# Integrated_Board_v1.net
KiCad netlist of a schematic drawn in EAGLE
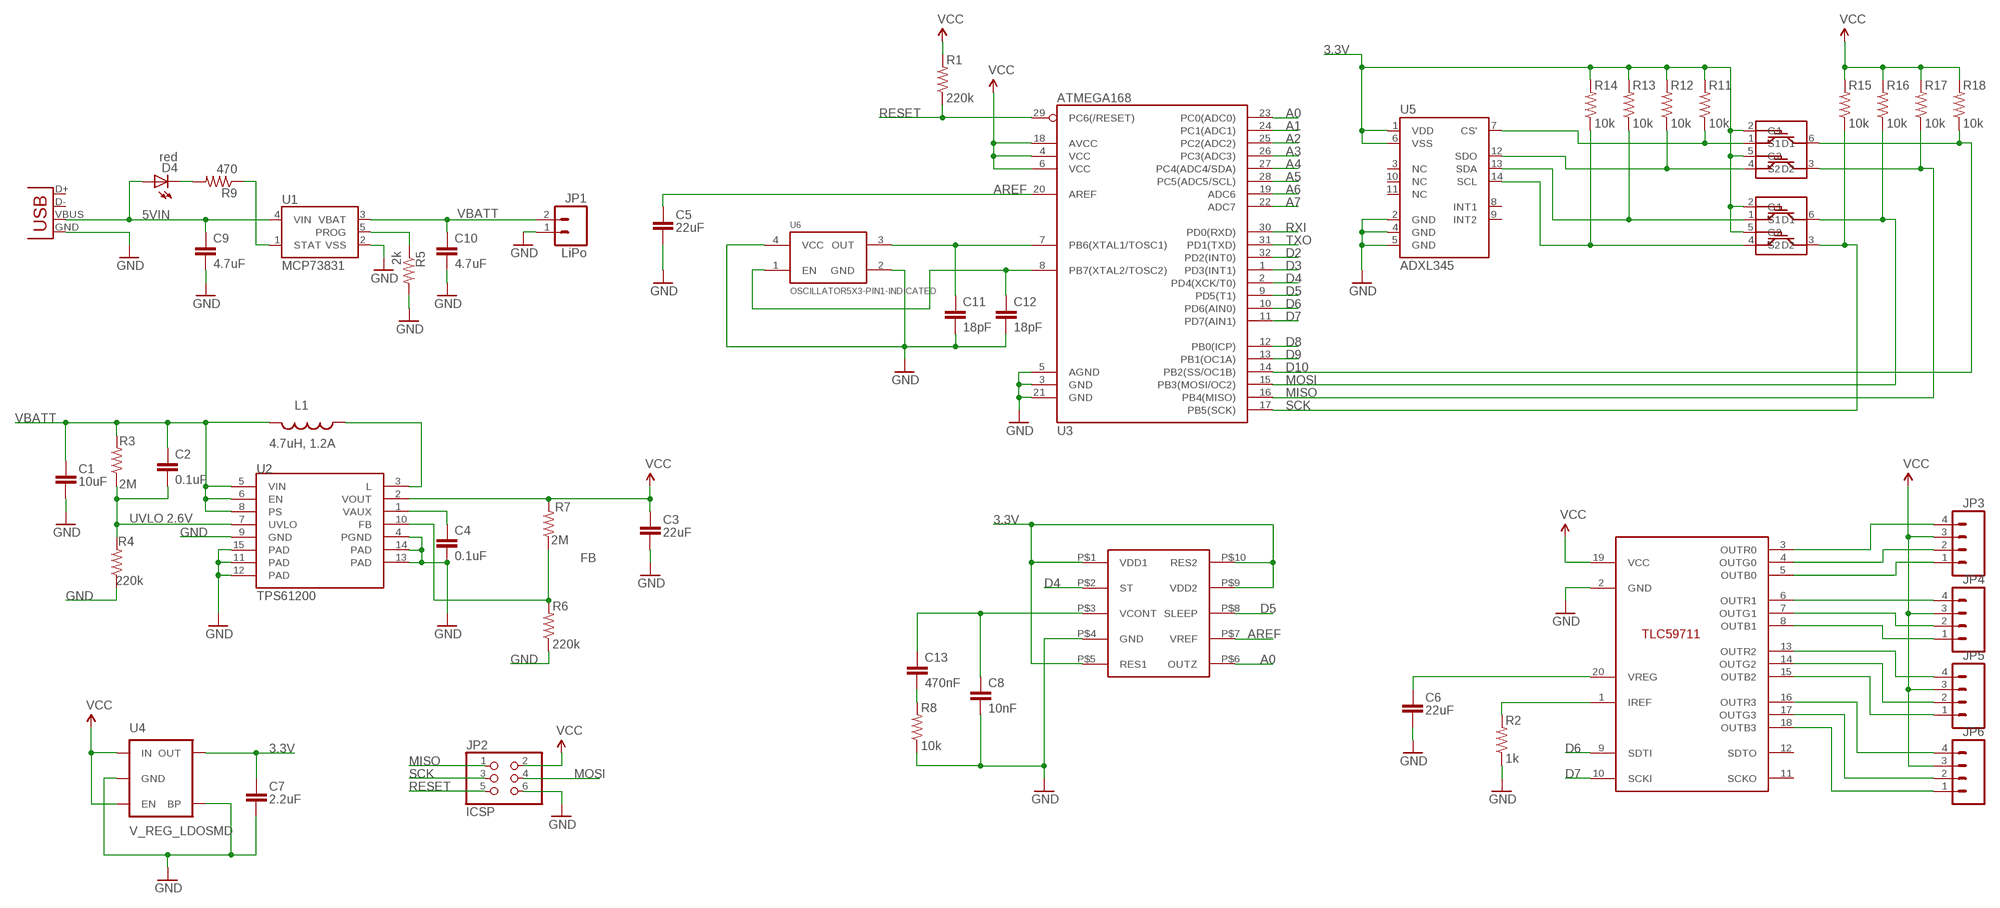
[diagram p0: schematic, sheet 1]

(export (version "E")
  (design (tool "Eeschema 10.0.6"))
  (components
    (comp (ref "C1")
      (value "10uF")
      (footprint "eagle-import:0603")
      (libsource (lib "eagle-import") (part "CAP0603"))
    )
    (comp (ref "C2")
      (value "0.1uF")
      (footprint "eagle-import:0603-CAP")
      (libsource (lib "eagle-import") (part "CAP0603-CAP"))
    )
    (comp (ref "C3")
      (value "22uF")
      (footprint "eagle-import:0805")
      (libsource (lib "eagle-import") (part "CAP0805"))
    )
    (comp (ref "C4")
      (value "0.1uF")
      (footprint "eagle-import:0603-CAP")
      (libsource (lib "eagle-import") (part "CAP0603-CAP"))
    )
    (comp (ref "C5")
      (value "22uF")
      (footprint "eagle-import:0805")
      (libsource (lib "eagle-import") (part "CAP0805"))
    )
    (comp (ref "C6")
      (value "22uF")
      (footprint "eagle-import:0805")
      (libsource (lib "eagle-import") (part "CAP0805"))
    )
    (comp (ref "C7")
      (value "2.2uF")
      (footprint "eagle-import:0603")
      (libsource (lib "eagle-import") (part "CAP0603"))
    )
    (comp (ref "C8")
      (value "10nF")
      (footprint "eagle-import:0603-CAP")
      (libsource (lib "eagle-import") (part "CAP0603-CAP"))
    )
    (comp (ref "C9")
      (value "4.7uF")
      (footprint "eagle-import:0603-CAP")
      (libsource (lib "eagle-import") (part "CAP0603-CAP"))
    )
    (comp (ref "C10")
      (value "4.7uF")
      (footprint "eagle-import:0603-CAP")
      (libsource (lib "eagle-import") (part "CAP0603-CAP"))
    )
    (comp (ref "C11")
      (value "18pF")
      (footprint "eagle-import:0603-CAP")
      (libsource (lib "eagle-import") (part "CAP0603-CAP"))
    )
    (comp (ref "C12")
      (value "18pF")
      (footprint "eagle-import:0603-CAP")
      (libsource (lib "eagle-import") (part "CAP0603-CAP"))
    )
    (comp (ref "C13")
      (value "470nF")
      (footprint "eagle-import:0603-CAP")
      (libsource (lib "eagle-import") (part "CAP0603-CAP"))
    )
    (comp (ref "D4")
      (value "red")
      (footprint "eagle-import:LED-0603")
      (libsource (lib "eagle-import") (part "LED0603"))
    )
    (comp (ref "JP1")
      (value "LiPo")
      (footprint "eagle-import:JST-2-SMD")
      (libsource (lib "eagle-import") (part "M02-JST-2MM-SMT"))
    )
    (comp (ref "JP2")
      (value "ICSP")
      (footprint "eagle-import:2X03")
      (libsource (lib "eagle-import") (part "PINHD-2X3"))
    )
    (comp (ref "JP3")
      (value "M04PTH")
      (footprint "eagle-import:1X04")
      (libsource (lib "eagle-import") (part "M04PTH"))
    )
    (comp (ref "JP4")
      (value "M04PTH")
      (footprint "eagle-import:1X04")
      (libsource (lib "eagle-import") (part "M04PTH"))
    )
    (comp (ref "JP5")
      (value "M04PTH")
      (footprint "eagle-import:1X04")
      (libsource (lib "eagle-import") (part "M04PTH"))
    )
    (comp (ref "JP6")
      (value "M04PTH")
      (footprint "eagle-import:1X04")
      (libsource (lib "eagle-import") (part "M04PTH"))
    )
    (comp (ref "L1")
      (value "4.7uH, 1.2A")
      (footprint "eagle-import:CDRH2D09")
      (libsource (lib "eagle-import") (part "INDUCTOR."))
    )
    (comp (ref "R1")
      (value "220k")
      (footprint "eagle-import:0603-RES")
      (libsource (lib "eagle-import") (part "RESISTOR0603-RES"))
    )
    (comp (ref "R2")
      (value "1k")
      (footprint "eagle-import:0603-RES")
      (libsource (lib "eagle-import") (part "RESISTOR0603-RES"))
    )
    (comp (ref "R3")
      (value "2M")
      (footprint "eagle-import:0603-RES")
      (libsource (lib "eagle-import") (part "RESISTOR0603-RES"))
    )
    (comp (ref "R4")
      (value "220k")
      (footprint "eagle-import:0603-RES")
      (libsource (lib "eagle-import") (part "RESISTOR0603-RES"))
    )
    (comp (ref "R5")
      (value "2k")
      (footprint "eagle-import:0603-RES")
      (libsource (lib "eagle-import") (part "RESISTOR0603-RES"))
    )
    (comp (ref "R6")
      (value "220k")
      (footprint "eagle-import:0603-RES")
      (libsource (lib "eagle-import") (part "RESISTOR0603-RES"))
    )
    (comp (ref "R7")
      (value "2M")
      (footprint "eagle-import:0603-RES")
      (libsource (lib "eagle-import") (part "RESISTOR0603-RES"))
    )
    (comp (ref "R8")
      (value "10k")
      (footprint "eagle-import:0603-RES")
      (libsource (lib "eagle-import") (part "RESISTOR0603-RES"))
    )
    (comp (ref "R9")
      (value "470")
      (footprint "eagle-import:0603-RES")
      (libsource (lib "eagle-import") (part "RESISTOR0603-RES"))
    )
    (comp (ref "R11")
      (value "10k")
      (footprint "eagle-import:0603-RES")
      (libsource (lib "eagle-import") (part "RESISTOR0603-RES"))
    )
    (comp (ref "R12")
      (value "10k")
      (footprint "eagle-import:0603-RES")
      (libsource (lib "eagle-import") (part "RESISTOR0603-RES"))
    )
    (comp (ref "R13")
      (value "10k")
      (footprint "eagle-import:0603-RES")
      (libsource (lib "eagle-import") (part "RESISTOR0603-RES"))
    )
    (comp (ref "R14")
      (value "10k")
      (footprint "eagle-import:0603-RES")
      (libsource (lib "eagle-import") (part "RESISTOR0603-RES"))
    )
    (comp (ref "R15")
      (value "10k")
      (footprint "eagle-import:0603-RES")
      (libsource (lib "eagle-import") (part "RESISTOR0603-RES"))
    )
    (comp (ref "R16")
      (value "10k")
      (footprint "eagle-import:0603-RES")
      (libsource (lib "eagle-import") (part "RESISTOR0603-RES"))
    )
    (comp (ref "R17")
      (value "10k")
      (footprint "eagle-import:0603-RES")
      (libsource (lib "eagle-import") (part "RESISTOR0603-RES"))
    )
    (comp (ref "R18")
      (value "10k")
      (footprint "eagle-import:0603-RES")
      (libsource (lib "eagle-import") (part "RESISTOR0603-RES"))
    )
    (comp (ref "U$1")
      (value "TLC59711")
      (footprint "eagle-import:TSSOP20")
      (libsource (lib "eagle-import") (part "TLC59711"))
    )
    (comp (ref "U$2")
      (value "2N7002DW")
      (footprint "eagle-import:SOT363")
      (libsource (lib "eagle-import") (part "2N7002DW"))
    )
    (comp (ref "U$3")
      (value "2N7002DW")
      (footprint "eagle-import:SOT363")
      (libsource (lib "eagle-import") (part "2N7002DW"))
    )
    (comp (ref "U$4")
      (value "LY3100ALH")
      (footprint "eagle-import:LGA10")
      (libsource (lib "eagle-import") (part "LY3100ALH"))
    )
    (comp (ref "U1")
      (value "MCP73831")
      (footprint "eagle-import:SOT23-5")
      (libsource (lib "eagle-import") (part "MCP73831"))
    )
    (comp (ref "U2")
      (value "TPS61200")
      (footprint "eagle-import:QFN-10_PAD")
      (libsource (lib "eagle-import") (part "TPS61200"))
    )
    (comp (ref "U3")
      (value "ATMEGA168")
      (footprint "eagle-import:TQFP32-08")
      (libsource (lib "eagle-import") (part "ATMEGA168"))
    )
    (comp (ref "U4")
      (value "V_REG_LDOSMD")
      (footprint "eagle-import:SOT23-5")
      (libsource (lib "eagle-import") (part "V_REG_LDOSMD"))
    )
    (comp (ref "U5")
      (value "ADXL345")
      (footprint "eagle-import:LGA14")
      (libsource (lib "eagle-import") (part "ADXL345"))
    )
    (comp (ref "U6")
      (value "OSCILLATOR5X3-PIN1-INDICATED")
      (footprint "eagle-import:CRYSTAL-OSC-SMD-5X3")
      (libsource (lib "eagle-import") (part "OSCILLATOR5X3-PIN1-INDICATED"))
    )
    (comp (ref "X1")
      (value "USB-MICROB")
      (footprint "eagle-import:USB-MICROB")
      (libsource (lib "eagle-import") (part "USB-MICROB"))
    )
  )
  (nets
    (net (code "1") (name "/3.3V") (class "Default")
      (node (ref "C7") (pin "1") (pinfunction "1_1") (pintype "passive"))
      (node (ref "R11") (pin "2") (pinfunction "2_2") (pintype "passive"))
      (node (ref "R12") (pin "2") (pinfunction "2_2") (pintype "passive"))
      (node (ref "R13") (pin "2") (pinfunction "2_2") (pintype "passive"))
      (node (ref "R14") (pin "2") (pinfunction "2_2") (pintype "passive"))
      (node (ref "U$2") (pin "2") (pinfunction "G1_2") (pintype "bidirectional"))
      (node (ref "U$2") (pin "5") (pinfunction "G2_5") (pintype "bidirectional"))
      (node (ref "U$3") (pin "2") (pinfunction "G1_2") (pintype "bidirectional"))
      (node (ref "U$3") (pin "5") (pinfunction "G2_5") (pintype "bidirectional"))
      (node (ref "U$4") (pin "P$1") (pinfunction "VDD1_P$1") (pintype "bidirectional"))
      (node (ref "U$4") (pin "P$10") (pinfunction "RES2_P$10") (pintype "bidirectional"))
      (node (ref "U$4") (pin "P$5") (pinfunction "RES1_P$5") (pintype "bidirectional"))
      (node (ref "U$4") (pin "P$9") (pinfunction "VDD2_P$9") (pintype "bidirectional"))
      (node (ref "U4") (pin "5") (pinfunction "OUT_5") (pintype "passive"))
      (node (ref "U5") (pin "1") (pinfunction "VDD_1") (pintype "bidirectional"))
      (node (ref "U5") (pin "6") (pinfunction "VSS_6") (pintype "bidirectional"))
    )
    (net (code "2") (name "/5VIN") (class "Default")
      (node (ref "C9") (pin "1") (pinfunction "1_1") (pintype "passive"))
      (node (ref "D4") (pin "A") (pinfunction "A_A") (pintype "passive"))
      (node (ref "U1") (pin "4") (pinfunction "VIN_4") (pintype "power_in"))
      (node (ref "X1") (pin "VBUS") (pinfunction "VBUS_VBUS") (pintype "bidirectional"))
    )
    (net (code "3") (name "/A0") (class "Default")
      (node (ref "U$4") (pin "P$6") (pinfunction "OUTZ_P$6") (pintype "bidirectional"))
      (node (ref "U3") (pin "23") (pinfunction "PC0(ADC0)_23") (pintype "bidirectional"))
    )
    (net (code "4") (name "/A1") (class "Default")
      (node (ref "U3") (pin "24") (pinfunction "PC1(ADC1)_24") (pintype "bidirectional"))
    )
    (net (code "5") (name "/A2") (class "Default")
      (node (ref "U3") (pin "25") (pinfunction "PC2(ADC2)_25") (pintype "bidirectional"))
    )
    (net (code "6") (name "/A3") (class "Default")
      (node (ref "U3") (pin "26") (pinfunction "PC3(ADC3)_26") (pintype "bidirectional"))
    )
    (net (code "7") (name "/A4") (class "Default")
      (node (ref "U3") (pin "27") (pinfunction "PC4(ADC4/SDA)_27") (pintype "bidirectional"))
    )
    (net (code "8") (name "/A5") (class "Default")
      (node (ref "U3") (pin "28") (pinfunction "PC5(ADC5/SCL)_28") (pintype "bidirectional"))
    )
    (net (code "9") (name "/A6") (class "Default")
      (node (ref "U3") (pin "19") (pinfunction "ADC6_19") (pintype "bidirectional"))
    )
    (net (code "10") (name "/A7") (class "Default")
      (node (ref "U3") (pin "22") (pinfunction "ADC7_22") (pintype "bidirectional"))
    )
    (net (code "11") (name "/AREF") (class "Default")
      (node (ref "C5") (pin "1") (pinfunction "1_1") (pintype "passive"))
      (node (ref "U$4") (pin "P$7") (pinfunction "VREF_P$7") (pintype "bidirectional"))
      (node (ref "U3") (pin "20") (pinfunction "AREF_20") (pintype "bidirectional"))
    )
    (net (code "12") (name "/D2") (class "Default")
      (node (ref "U3") (pin "32") (pinfunction "PD2(INT0)_32") (pintype "bidirectional"))
    )
    (net (code "13") (name "/D3") (class "Default")
      (node (ref "U3") (pin "1") (pinfunction "PD3(INT1)_1") (pintype "bidirectional"))
    )
    (net (code "14") (name "/D4") (class "Default")
      (node (ref "U$4") (pin "P$2") (pinfunction "ST_P$2") (pintype "bidirectional"))
      (node (ref "U3") (pin "2") (pinfunction "PD4(XCK/T0)_2") (pintype "bidirectional"))
    )
    (net (code "15") (name "/D5") (class "Default")
      (node (ref "U$4") (pin "P$8") (pinfunction "SLEEP_P$8") (pintype "bidirectional"))
      (node (ref "U3") (pin "9") (pinfunction "PD5(T1)_9") (pintype "bidirectional"))
    )
    (net (code "16") (name "/D6") (class "Default")
      (node (ref "U$1") (pin "9") (pinfunction "SDTI_9") (pintype "bidirectional"))
      (node (ref "U3") (pin "10") (pinfunction "PD6(AIN0)_10") (pintype "bidirectional"))
    )
    (net (code "17") (name "/D7") (class "Default")
      (node (ref "U$1") (pin "10") (pinfunction "SCKI_10") (pintype "bidirectional"))
      (node (ref "U3") (pin "11") (pinfunction "PD7(AIN1)_11") (pintype "bidirectional"))
    )
    (net (code "18") (name "/D8") (class "Default")
      (node (ref "U3") (pin "12") (pinfunction "PB0(ICP)_12") (pintype "bidirectional"))
    )
    (net (code "19") (name "/D9") (class "Default")
      (node (ref "U3") (pin "13") (pinfunction "PB1(OC1A)_13") (pintype "bidirectional"))
    )
    (net (code "20") (name "/D10") (class "Default")
      (node (ref "R18") (pin "1") (pinfunction "1_1") (pintype "passive"))
      (node (ref "U$2") (pin "6") (pinfunction "D1_6") (pintype "bidirectional"))
      (node (ref "U3") (pin "14") (pinfunction "PB2(SS/OC1B)_14") (pintype "bidirectional"))
    )
    (net (code "21") (name "/FB") (class "Default")
      (node (ref "R6") (pin "2") (pinfunction "2_2") (pintype "passive"))
      (node (ref "R7") (pin "1") (pinfunction "1_1") (pintype "passive"))
      (node (ref "U2") (pin "10") (pinfunction "FB_10") (pintype "passive"))
    )
    (net (code "22") (name "/MISO") (class "Default")
      (node (ref "JP2") (pin "1") (pinfunction "1_1") (pintype "passive"))
      (node (ref "R17") (pin "1") (pinfunction "1_1") (pintype "passive"))
      (node (ref "U$2") (pin "3") (pinfunction "D2_3") (pintype "bidirectional"))
      (node (ref "U3") (pin "16") (pinfunction "PB4(MISO)_16") (pintype "bidirectional"))
    )
    (net (code "23") (name "/MOSI") (class "Default")
      (node (ref "JP2") (pin "4") (pinfunction "4_4") (pintype "passive"))
      (node (ref "R16") (pin "1") (pinfunction "1_1") (pintype "passive"))
      (node (ref "U$3") (pin "6") (pinfunction "D1_6") (pintype "bidirectional"))
      (node (ref "U3") (pin "15") (pinfunction "PB3(MOSI/OC2)_15") (pintype "bidirectional"))
    )
    (net (code "24") (name "/RESET") (class "Default")
      (node (ref "JP2") (pin "5") (pinfunction "5_5") (pintype "passive"))
      (node (ref "R1") (pin "1") (pinfunction "1_1") (pintype "passive"))
      (node (ref "U3") (pin "29") (pinfunction "PC6(/RESET)_29") (pintype "bidirectional"))
    )
    (net (code "25") (name "/RXI") (class "Default")
      (node (ref "U3") (pin "30") (pinfunction "PD0(RXD)_30") (pintype "bidirectional"))
    )
    (net (code "26") (name "/SCK") (class "Default")
      (node (ref "JP2") (pin "3") (pinfunction "3_3") (pintype "passive"))
      (node (ref "R15") (pin "1") (pinfunction "1_1") (pintype "passive"))
      (node (ref "U$3") (pin "3") (pinfunction "D2_3") (pintype "bidirectional"))
      (node (ref "U3") (pin "17") (pinfunction "PB5(SCK)_17") (pintype "bidirectional"))
    )
    (net (code "27") (name "/TXO") (class "Default")
      (node (ref "U3") (pin "31") (pinfunction "PD1(TXD)_31") (pintype "bidirectional"))
    )
    (net (code "28") (name "/VBATT") (class "Default")
      (node (ref "C1") (pin "1") (pinfunction "1_1") (pintype "passive"))
      (node (ref "C10") (pin "1") (pinfunction "1_1") (pintype "passive"))
      (node (ref "C2") (pin "1") (pinfunction "1_1") (pintype "passive"))
      (node (ref "JP1") (pin "2") (pinfunction "2_2") (pintype "passive"))
      (node (ref "L1") (pin "P$2") (pinfunction "2_P$2") (pintype "passive"))
      (node (ref "R3") (pin "2") (pinfunction "2_2") (pintype "passive"))
      (node (ref "U1") (pin "3") (pinfunction "VBAT_3") (pintype "power_in"))
      (node (ref "U2") (pin "5") (pinfunction "VIN_5") (pintype "power_in"))
      (node (ref "U2") (pin "6") (pinfunction "EN_6") (pintype "input"))
      (node (ref "U2") (pin "8") (pinfunction "PS_8") (pintype "input"))
    )
    (net (code "29") (name "GND") (class "Default")
      (node (ref "C1") (pin "2") (pinfunction "2_2") (pintype "passive"))
      (node (ref "C10") (pin "2") (pinfunction "2_2") (pintype "passive"))
      (node (ref "C11") (pin "2") (pinfunction "2_2") (pintype "passive"))
      (node (ref "C12") (pin "2") (pinfunction "2_2") (pintype "passive"))
      (node (ref "C3") (pin "2") (pinfunction "2_2") (pintype "passive"))
      (node (ref "C4") (pin "2") (pinfunction "2_2") (pintype "passive"))
      (node (ref "C5") (pin "2") (pinfunction "2_2") (pintype "passive"))
      (node (ref "C6") (pin "2") (pinfunction "2_2") (pintype "passive"))
      (node (ref "C7") (pin "2") (pinfunction "2_2") (pintype "passive"))
      (node (ref "C8") (pin "2") (pinfunction "2_2") (pintype "passive"))
      (node (ref "C9") (pin "2") (pinfunction "2_2") (pintype "passive"))
      (node (ref "JP1") (pin "1") (pinfunction "1_1") (pintype "passive"))
      (node (ref "JP2") (pin "6") (pinfunction "6_6") (pintype "passive"))
      (node (ref "R2") (pin "1") (pinfunction "1_1") (pintype "passive"))
      (node (ref "R4") (pin "1") (pinfunction "1_1") (pintype "passive"))
      (node (ref "R5") (pin "2") (pinfunction "2_2") (pintype "passive"))
      (node (ref "R6") (pin "1") (pinfunction "1_1") (pintype "passive"))
      (node (ref "R8") (pin "1") (pinfunction "1_1") (pintype "passive"))
      (node (ref "U$1") (pin "2") (pinfunction "GND_2") (pintype "bidirectional"))
      (node (ref "U$4") (pin "P$4") (pinfunction "GND_P$4") (pintype "bidirectional"))
      (node (ref "U1") (pin "2") (pinfunction "VSS_2") (pintype "power_in"))
      (node (ref "U2") (pin "11") (pinfunction "PAD_11") (pintype "power_in"))
      (node (ref "U2") (pin "12") (pinfunction "PAD_12") (pintype "power_in"))
      (node (ref "U2") (pin "13") (pinfunction "PAD_13") (pintype "power_in"))
      (node (ref "U2") (pin "14") (pinfunction "PAD_14") (pintype "power_in"))
      (node (ref "U2") (pin "15") (pinfunction "PAD_15") (pintype "power_in"))
      (node (ref "U2") (pin "4") (pinfunction "PGND_4") (pintype "power_in"))
      (node (ref "U2") (pin "9") (pinfunction "GND_9") (pintype "power_in"))
      (node (ref "U3") (pin "21") (pinfunction "GND_21") (pintype "bidirectional"))
      (node (ref "U3") (pin "3") (pinfunction "GND_3") (pintype "bidirectional"))
      (node (ref "U3") (pin "5") (pinfunction "AGND_5") (pintype "bidirectional"))
      (node (ref "U4") (pin "2") (pinfunction "GND_2") (pintype "input"))
      (node (ref "U4") (pin "4") (pinfunction "BP_4") (pintype "input"))
      (node (ref "U5") (pin "2") (pinfunction "GND_2") (pintype "bidirectional"))
      (node (ref "U5") (pin "4") (pinfunction "GND_4") (pintype "bidirectional"))
      (node (ref "U5") (pin "5") (pinfunction "GND_5") (pintype "bidirectional"))
      (node (ref "U6") (pin "2") (pinfunction "GND_2") (pintype "bidirectional"))
      (node (ref "U6") (pin "4") (pinfunction "VCC_4") (pintype "bidirectional"))
      (node (ref "X1") (pin "GND") (pinfunction "GND_GND") (pintype "bidirectional"))
    )
    (net (code "30") (name "Net-(C13-Pad2)") (class "Default")
      (node (ref "C13") (pin "2") (pinfunction "2_2") (pintype "passive"))
      (node (ref "R8") (pin "2") (pinfunction "2_2") (pintype "passive"))
    )
    (net (code "31") (name "Net-(D4-PadC)") (class "Default")
      (node (ref "D4") (pin "C") (pinfunction "C_C") (pintype "passive"))
      (node (ref "R9") (pin "2") (pinfunction "2_2") (pintype "passive"))
    )
    (net (code "32") (name "Net-(JP3-B)") (class "Default")
      (node (ref "JP3") (pin "4") (pinfunction "B_4") (pintype "passive"))
      (node (ref "U$1") (pin "3") (pinfunction "OUTR0_3") (pintype "bidirectional"))
    )
    (net (code "33") (name "Net-(JP3-COM)") (class "Default")
      (node (ref "JP3") (pin "1") (pinfunction "COM_1") (pintype "passive"))
      (node (ref "U$1") (pin "5") (pinfunction "OUTB0_5") (pintype "bidirectional"))
    )
    (net (code "34") (name "Net-(JP3-R)") (class "Default")
      (node (ref "JP3") (pin "2") (pinfunction "R_2") (pintype "passive"))
      (node (ref "U$1") (pin "4") (pinfunction "OUTG0_4") (pintype "bidirectional"))
    )
    (net (code "35") (name "Net-(JP4-B)") (class "Default")
      (node (ref "JP4") (pin "4") (pinfunction "B_4") (pintype "passive"))
      (node (ref "U$1") (pin "6") (pinfunction "OUTR1_6") (pintype "bidirectional"))
    )
    (net (code "36") (name "Net-(JP4-COM)") (class "Default")
      (node (ref "JP4") (pin "1") (pinfunction "COM_1") (pintype "passive"))
      (node (ref "U$1") (pin "8") (pinfunction "OUTB1_8") (pintype "bidirectional"))
    )
    (net (code "37") (name "Net-(JP4-R)") (class "Default")
      (node (ref "JP4") (pin "2") (pinfunction "R_2") (pintype "passive"))
      (node (ref "U$1") (pin "7") (pinfunction "OUTG1_7") (pintype "bidirectional"))
    )
    (net (code "38") (name "Net-(JP5-B)") (class "Default")
      (node (ref "JP5") (pin "4") (pinfunction "B_4") (pintype "passive"))
      (node (ref "U$1") (pin "13") (pinfunction "OUTR2_13") (pintype "bidirectional"))
    )
    (net (code "39") (name "Net-(JP5-COM)") (class "Default")
      (node (ref "JP5") (pin "1") (pinfunction "COM_1") (pintype "passive"))
      (node (ref "U$1") (pin "15") (pinfunction "OUTB2_15") (pintype "bidirectional"))
    )
    (net (code "40") (name "Net-(JP5-R)") (class "Default")
      (node (ref "JP5") (pin "2") (pinfunction "R_2") (pintype "passive"))
      (node (ref "U$1") (pin "14") (pinfunction "OUTG2_14") (pintype "bidirectional"))
    )
    (net (code "41") (name "Net-(JP6-B)") (class "Default")
      (node (ref "JP6") (pin "4") (pinfunction "B_4") (pintype "passive"))
      (node (ref "U$1") (pin "16") (pinfunction "OUTR3_16") (pintype "bidirectional"))
    )
    (net (code "42") (name "Net-(JP6-COM)") (class "Default")
      (node (ref "JP6") (pin "1") (pinfunction "COM_1") (pintype "passive"))
      (node (ref "U$1") (pin "18") (pinfunction "OUTB3_18") (pintype "bidirectional"))
    )
    (net (code "43") (name "Net-(JP6-R)") (class "Default")
      (node (ref "JP6") (pin "2") (pinfunction "R_2") (pintype "passive"))
      (node (ref "U$1") (pin "17") (pinfunction "OUTG3_17") (pintype "bidirectional"))
    )
    (net (code "44") (name "Net-(L1-1)") (class "Default")
      (node (ref "L1") (pin "P$1") (pinfunction "1_P$1") (pintype "passive"))
      (node (ref "U2") (pin "3") (pinfunction "L_3") (pintype "passive"))
    )
    (net (code "45") (name "Net-(U$1-IREF)") (class "Default")
      (node (ref "R2") (pin "2") (pinfunction "2_2") (pintype "passive"))
      (node (ref "U$1") (pin "1") (pinfunction "IREF_1") (pintype "bidirectional"))
    )
    (net (code "46") (name "Net-(U$1-VREG)") (class "Default")
      (node (ref "C6") (pin "1") (pinfunction "1_1") (pintype "passive"))
      (node (ref "U$1") (pin "20") (pinfunction "VREG_20") (pintype "bidirectional"))
    )
    (net (code "47") (name "Net-(U$2-S1)") (class "Default")
      (node (ref "R11") (pin "1") (pinfunction "1_1") (pintype "passive"))
      (node (ref "U$2") (pin "1") (pinfunction "S1_1") (pintype "bidirectional"))
      (node (ref "U5") (pin "7") (pinfunction "CS'_7") (pintype "bidirectional"))
    )
    (net (code "48") (name "Net-(U$2-S2)") (class "Default")
      (node (ref "R12") (pin "1") (pinfunction "1_1") (pintype "passive"))
      (node (ref "U$2") (pin "4") (pinfunction "S2_4") (pintype "bidirectional"))
      (node (ref "U5") (pin "12") (pinfunction "SDO_12") (pintype "bidirectional"))
    )
    (net (code "49") (name "Net-(U$3-S1)") (class "Default")
      (node (ref "R13") (pin "1") (pinfunction "1_1") (pintype "passive"))
      (node (ref "U$3") (pin "1") (pinfunction "S1_1") (pintype "bidirectional"))
      (node (ref "U5") (pin "13") (pinfunction "SDA_13") (pintype "bidirectional"))
    )
    (net (code "50") (name "Net-(U$3-S2)") (class "Default")
      (node (ref "R14") (pin "1") (pinfunction "1_1") (pintype "passive"))
      (node (ref "U$3") (pin "4") (pinfunction "S2_4") (pintype "bidirectional"))
      (node (ref "U5") (pin "14") (pinfunction "SCL_14") (pintype "bidirectional"))
    )
    (net (code "51") (name "Net-(U$4-VCONT)") (class "Default")
      (node (ref "C13") (pin "1") (pinfunction "1_1") (pintype "passive"))
      (node (ref "C8") (pin "1") (pinfunction "1_1") (pintype "passive"))
      (node (ref "U$4") (pin "P$3") (pinfunction "VCONT_P$3") (pintype "bidirectional"))
    )
    (net (code "52") (name "Net-(U1-PROG)") (class "Default")
      (node (ref "R5") (pin "1") (pinfunction "1_1") (pintype "passive"))
      (node (ref "U1") (pin "5") (pinfunction "PROG_5") (pintype "input"))
    )
    (net (code "53") (name "Net-(U1-STAT)") (class "Default")
      (node (ref "R9") (pin "1") (pinfunction "1_1") (pintype "passive"))
      (node (ref "U1") (pin "1") (pinfunction "STAT_1") (pintype "output"))
    )
    (net (code "54") (name "Net-(U2-UVLO)") (class "Default")
      (node (ref "C2") (pin "2") (pinfunction "2_2") (pintype "passive"))
      (node (ref "R3") (pin "1") (pinfunction "1_1") (pintype "passive"))
      (node (ref "R4") (pin "2") (pinfunction "2_2") (pintype "passive"))
      (node (ref "U2") (pin "7") (pinfunction "UVLO_7") (pintype "passive"))
    )
    (net (code "55") (name "Net-(U2-VAUX)") (class "Default")
      (node (ref "C4") (pin "1") (pinfunction "1_1") (pintype "passive"))
      (node (ref "U2") (pin "1") (pinfunction "VAUX_1") (pintype "passive"))
    )
    (net (code "56") (name "Net-(U3-PB6(XTAL1{slash}TOSC1))") (class "Default")
      (node (ref "C11") (pin "1") (pinfunction "1_1") (pintype "passive"))
      (node (ref "U3") (pin "7") (pinfunction "PB6(XTAL1/TOSC1)_7") (pintype "bidirectional"))
      (node (ref "U6") (pin "3") (pinfunction "OUT_3") (pintype "bidirectional"))
    )
    (net (code "57") (name "Net-(U3-PB7(XTAL2{slash}TOSC2))") (class "Default")
      (node (ref "C12") (pin "1") (pinfunction "1_1") (pintype "passive"))
      (node (ref "U3") (pin "8") (pinfunction "PB7(XTAL2/TOSC2)_8") (pintype "bidirectional"))
      (node (ref "U6") (pin "1") (pinfunction "EN_1") (pintype "bidirectional"))
    )
    (net (code "58") (name "VCC") (class "Default")
      (node (ref "C3") (pin "1") (pinfunction "1_1") (pintype "passive"))
      (node (ref "JP2") (pin "2") (pinfunction "2_2") (pintype "passive"))
      (node (ref "JP3") (pin "3") (pinfunction "G_3") (pintype "passive"))
      (node (ref "JP4") (pin "3") (pinfunction "G_3") (pintype "passive"))
      (node (ref "JP5") (pin "3") (pinfunction "G_3") (pintype "passive"))
      (node (ref "JP6") (pin "3") (pinfunction "G_3") (pintype "passive"))
      (node (ref "R1") (pin "2") (pinfunction "2_2") (pintype "passive"))
      (node (ref "R15") (pin "2") (pinfunction "2_2") (pintype "passive"))
      (node (ref "R16") (pin "2") (pinfunction "2_2") (pintype "passive"))
      (node (ref "R17") (pin "2") (pinfunction "2_2") (pintype "passive"))
      (node (ref "R18") (pin "2") (pinfunction "2_2") (pintype "passive"))
      (node (ref "R7") (pin "2") (pinfunction "2_2") (pintype "passive"))
      (node (ref "U$1") (pin "19") (pinfunction "VCC_19") (pintype "bidirectional"))
      (node (ref "U2") (pin "2") (pinfunction "VOUT_2") (pintype "passive"))
      (node (ref "U3") (pin "18") (pinfunction "AVCC_18") (pintype "bidirectional"))
      (node (ref "U3") (pin "4") (pinfunction "VCC_4") (pintype "bidirectional"))
      (node (ref "U3") (pin "6") (pinfunction "VCC_6") (pintype "bidirectional"))
      (node (ref "U4") (pin "1") (pinfunction "IN_1") (pintype "input"))
      (node (ref "U4") (pin "3") (pinfunction "EN_3") (pintype "input"))
    )
    (net (code "59") (name "unconnected-(U$1-SCKO-Pad11)") (class "Default")
      (node (ref "U$1") (pin "11") (pinfunction "SCKO_11") (pintype "bidirectional"))
    )
    (net (code "60") (name "unconnected-(U$1-SDTO-Pad12)") (class "Default")
      (node (ref "U$1") (pin "12") (pinfunction "SDTO_12") (pintype "bidirectional"))
    )
    (net (code "61") (name "unconnected-(U5-INT1-Pad8)") (class "Default")
      (node (ref "U5") (pin "8") (pinfunction "INT1_8") (pintype "bidirectional"))
    )
    (net (code "62") (name "unconnected-(U5-INT2-Pad9)") (class "Default")
      (node (ref "U5") (pin "9") (pinfunction "INT2_9") (pintype "bidirectional"))
    )
    (net (code "63") (name "unconnected-(U5-NC-Pad3)") (class "Default")
      (node (ref "U5") (pin "3") (pinfunction "NC_3") (pintype "bidirectional"))
    )
    (net (code "64") (name "unconnected-(U5-NC-Pad10)") (class "Default")
      (node (ref "U5") (pin "10") (pinfunction "NC_10") (pintype "bidirectional"))
    )
    (net (code "65") (name "unconnected-(U5-NC-Pad11)") (class "Default")
      (node (ref "U5") (pin "11") (pinfunction "NC_11") (pintype "bidirectional"))
    )
    (net (code "66") (name "unconnected-(X1-PadD+)") (class "Default")
      (node (ref "X1") (pin "D+") (pinfunction "D+_D+") (pintype "bidirectional"))
    )
    (net (code "67") (name "unconnected-(X1-PadD-)") (class "Default")
      (node (ref "X1") (pin "D-") (pinfunction "D-_D-") (pintype "bidirectional"))
    )
  )
)
